# Koala_Bear_test_jig.net
KiCad netlist of a schematic drawn in EAGLE
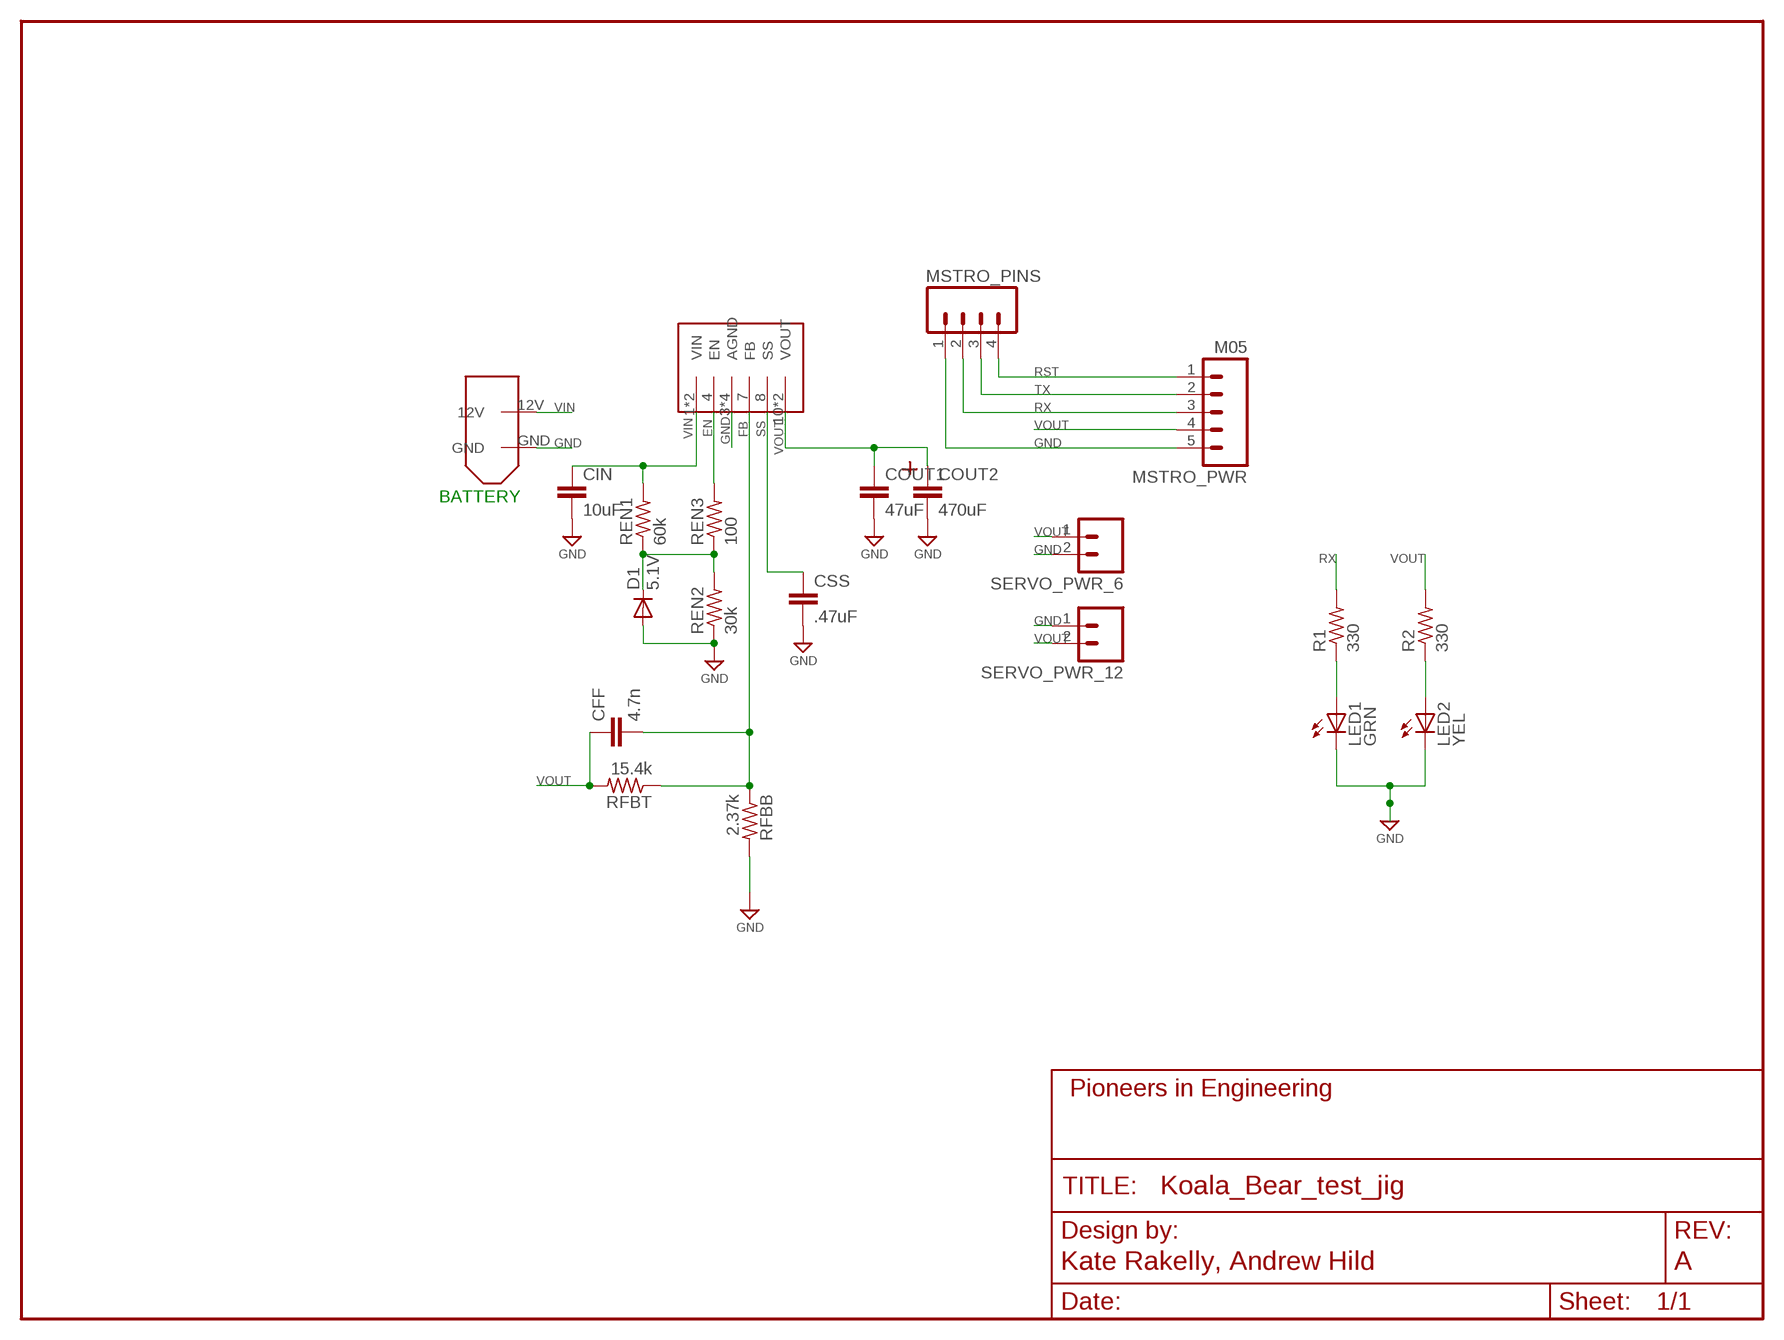
[diagram p0: schematic, sheet 1]

(export (version "E")
  (design (tool "Eeschema 10.0.6"))
  (components
    (comp (ref "CFF")
      (value "4.7n")
      (footprint "eagle-import:0603-CAP")
      (libsource (lib "eagle-import") (part "pie_CAP0603-CAP"))
    )
    (comp (ref "CIN")
      (value "10uF")
      (footprint "eagle-import:0603-CAP")
      (libsource (lib "eagle-import") (part "pie_CAP0603-CAP"))
    )
    (comp (ref "COUT1")
      (value "47uF")
      (footprint "eagle-import:1206")
      (libsource (lib "eagle-import") (part "CAP1206"))
    )
    (comp (ref "COUT2")
      (value "470uF")
      (footprint "eagle-import:TANT_CASE_E")
      (libsource (lib "eagle-import") (part "TANT_CASE_E"))
    )
    (comp (ref "CSS")
      (value ".47uF")
      (footprint "eagle-import:0603-CAP")
      (libsource (lib "eagle-import") (part "pie_CAP0603-CAP"))
    )
    (comp (ref "D1")
      (value "5.1V")
      (footprint "eagle-import:SOD-323")
      (libsource (lib "eagle-import") (part "DIODESOD"))
    )
    (comp (ref "LED1")
      (value "GRN")
      (footprint "eagle-import:CHIP-LED0805")
      (libsource (lib "eagle-import") (part "LEDCHIP-LED0805"))
    )
    (comp (ref "LED2")
      (value "YEL")
      (footprint "eagle-import:CHIP-LED0805")
      (libsource (lib "eagle-import") (part "LEDCHIP-LED0805"))
    )
    (comp (ref "MSTRO_PINS")
      (value "M041X04-MTA")
      (footprint "eagle-import:1X04-MTA")
      (fields (field (name "PARTNUMBER") "A1922-ND"))
      (libsource (lib "eagle-import") (part "M041X04-MTA"))
    )
    (comp (ref "MSTRO_PWR")
      (value "M05")
      (footprint "eagle-import:1X05-MTA")
      (libsource (lib "eagle-import") (part "M05"))
    )
    (comp (ref "R1")
      (value "330")
      (footprint "eagle-import:R0603")
      (libsource (lib "eagle-import") (part "rcl_R-US_R0603"))
    )
    (comp (ref "R2")
      (value "330")
      (footprint "eagle-import:R0603")
      (libsource (lib "eagle-import") (part "rcl_R-US_R0603"))
    )
    (comp (ref "REN1")
      (value "60k")
      (footprint "eagle-import:R0603")
      (libsource (lib "eagle-import") (part "R-US_R0603"))
    )
    (comp (ref "REN2")
      (value "30k")
      (footprint "eagle-import:R0603")
      (libsource (lib "eagle-import") (part "R-US_R0603"))
    )
    (comp (ref "REN3")
      (value "100")
      (footprint "eagle-import:R0603")
      (libsource (lib "eagle-import") (part "R-US_R0603"))
    )
    (comp (ref "RFBB")
      (value "2.37k")
      (footprint "eagle-import:R0603")
      (libsource (lib "eagle-import") (part "R-US_R0603"))
    )
    (comp (ref "RFBT")
      (value "15.4k")
      (footprint "eagle-import:R0603")
      (libsource (lib "eagle-import") (part "R-US_R0603"))
    )
    (comp (ref "SERVO_PWR_6")
      (value "M02PTH")
      (footprint "eagle-import:1X02")
      (libsource (lib "eagle-import") (part "M02PTH"))
    )
    (comp (ref "SERVO_PWR_12")
      (value "M02PTH")
      (footprint "eagle-import:1X02")
      (libsource (lib "eagle-import") (part "M02PTH"))
    )
    (comp (ref "U$1")
      (value "LMZ12010")
      (footprint "eagle-import:LMZ12010")
      (libsource (lib "eagle-import") (part "LMZ12010"))
    )
    (comp (ref "XT60")
      (value "XT60CONNECTOR")
      (footprint "eagle-import:XT60CONNECTOR")
      (fields (field (name "PARTNUMBER") "PRT-10474 "))
      (libsource (lib "eagle-import") (part "XT60CONNECTOR"))
    )
  )
  (nets
    (net (code "1") (name "/EN") (class "Default")
      (node (ref "REN3") (pin "2") (pinfunction "2_2") (pintype "passive"))
      (node (ref "U$1") (pin "4") (pinfunction "EN_4") (pintype "bidirectional"))
    )
    (net (code "2") (name "/FB") (class "Default")
      (node (ref "CFF") (pin "2") (pinfunction "2_2") (pintype "passive"))
      (node (ref "RFBB") (pin "1") (pinfunction "1_1") (pintype "passive"))
      (node (ref "RFBT") (pin "1") (pinfunction "1_1") (pintype "passive"))
      (node (ref "U$1") (pin "7") (pinfunction "FB_7") (pintype "bidirectional"))
    )
    (net (code "3") (name "/RST") (class "Default")
      (node (ref "MSTRO_PINS") (pin "4") (pinfunction "4_4") (pintype "passive"))
      (node (ref "MSTRO_PWR") (pin "1") (pinfunction "1_1") (pintype "passive"))
    )
    (net (code "4") (name "/RX") (class "Default")
      (node (ref "MSTRO_PINS") (pin "2") (pinfunction "2_2") (pintype "passive"))
      (node (ref "MSTRO_PWR") (pin "3") (pinfunction "3_3") (pintype "passive"))
      (node (ref "R1") (pin "2") (pinfunction "2_2") (pintype "passive"))
    )
    (net (code "5") (name "/SS") (class "Default")
      (node (ref "CSS") (pin "1") (pinfunction "1_1") (pintype "passive"))
      (node (ref "U$1") (pin "8") (pinfunction "SS_8") (pintype "bidirectional"))
    )
    (net (code "6") (name "/TX") (class "Default")
      (node (ref "MSTRO_PINS") (pin "3") (pinfunction "3_3") (pintype "passive"))
      (node (ref "MSTRO_PWR") (pin "2") (pinfunction "2_2") (pintype "passive"))
    )
    (net (code "7") (name "/VIN") (class "Default")
      (node (ref "CIN") (pin "1") (pinfunction "1_1") (pintype "passive"))
      (node (ref "REN1") (pin "2") (pinfunction "2_2") (pintype "passive"))
      (node (ref "U$1") (pin "1") (pinfunction "VIN_1") (pintype "bidirectional"))
      (node (ref "U$1") (pin "2") (pinfunction "VIN_2") (pintype "bidirectional"))
      (node (ref "XT60") (pin "12V") (pinfunction "12V_12V") (pintype "bidirectional"))
    )
    (net (code "8") (name "/VOUT") (class "Default")
      (node (ref "CFF") (pin "1") (pinfunction "1_1") (pintype "passive"))
      (node (ref "COUT1") (pin "1") (pinfunction "1_1") (pintype "passive"))
      (node (ref "COUT2") (pin "POS") (pinfunction "POS_POS") (pintype "passive"))
      (node (ref "MSTRO_PWR") (pin "4") (pinfunction "4_4") (pintype "passive"))
      (node (ref "R2") (pin "2") (pinfunction "2_2") (pintype "passive"))
      (node (ref "RFBT") (pin "2") (pinfunction "2_2") (pintype "passive"))
      (node (ref "SERVO_PWR_12") (pin "2") (pinfunction "2_2") (pintype "passive"))
      (node (ref "SERVO_PWR_6") (pin "1") (pinfunction "1_1") (pintype "passive"))
      (node (ref "U$1") (pin "10") (pinfunction "VOUT_10") (pintype "bidirectional"))
      (node (ref "U$1") (pin "11") (pinfunction "VOUT_11") (pintype "bidirectional"))
    )
    (net (code "9") (name "GND") (class "Default")
      (node (ref "CIN") (pin "2") (pinfunction "2_2") (pintype "passive"))
      (node (ref "COUT1") (pin "2") (pinfunction "2_2") (pintype "passive"))
      (node (ref "COUT2") (pin "NEG") (pinfunction "NEG_NEG") (pintype "passive"))
      (node (ref "CSS") (pin "2") (pinfunction "2_2") (pintype "passive"))
      (node (ref "D1") (pin "2") (pinfunction "A_2") (pintype "passive"))
      (node (ref "LED1") (pin "C") (pinfunction "C_C") (pintype "passive"))
      (node (ref "LED2") (pin "C") (pinfunction "C_C") (pintype "passive"))
      (node (ref "MSTRO_PINS") (pin "1") (pinfunction "1_1") (pintype "passive"))
      (node (ref "MSTRO_PWR") (pin "5") (pinfunction "5_5") (pintype "passive"))
      (node (ref "REN2") (pin "1") (pinfunction "1_1") (pintype "passive"))
      (node (ref "RFBB") (pin "2") (pinfunction "2_2") (pintype "passive"))
      (node (ref "SERVO_PWR_12") (pin "1") (pinfunction "1_1") (pintype "passive"))
      (node (ref "SERVO_PWR_6") (pin "2") (pinfunction "2_2") (pintype "passive"))
      (node (ref "U$1") (pin "3") (pinfunction "AGND_3") (pintype "bidirectional"))
      (node (ref "U$1") (pin "5") (pinfunction "AGND_5") (pintype "bidirectional"))
      (node (ref "U$1") (pin "6") (pinfunction "AGND_6") (pintype "bidirectional"))
      (node (ref "U$1") (pin "GND") (pinfunction "AGND_GND") (pintype "bidirectional"))
      (node (ref "XT60") (pin "GND") (pinfunction "GND_GND") (pintype "bidirectional"))
    )
    (net (code "10") (name "Net-(D1-C)") (class "Default")
      (node (ref "D1") (pin "1") (pinfunction "C_1") (pintype "passive"))
      (node (ref "REN1") (pin "1") (pinfunction "1_1") (pintype "passive"))
      (node (ref "REN2") (pin "2") (pinfunction "2_2") (pintype "passive"))
      (node (ref "REN3") (pin "1") (pinfunction "1_1") (pintype "passive"))
    )
    (net (code "11") (name "Net-(LED1-PadA)") (class "Default")
      (node (ref "LED1") (pin "A") (pinfunction "A_A") (pintype "passive"))
      (node (ref "R1") (pin "1") (pinfunction "1_1") (pintype "passive"))
    )
    (net (code "12") (name "Net-(LED2-PadA)") (class "Default")
      (node (ref "LED2") (pin "A") (pinfunction "A_A") (pintype "passive"))
      (node (ref "R2") (pin "1") (pinfunction "1_1") (pintype "passive"))
    )
  )
)
